# Sch_Power.net
KiCad netlist of a schematic drawn in Altium Designer
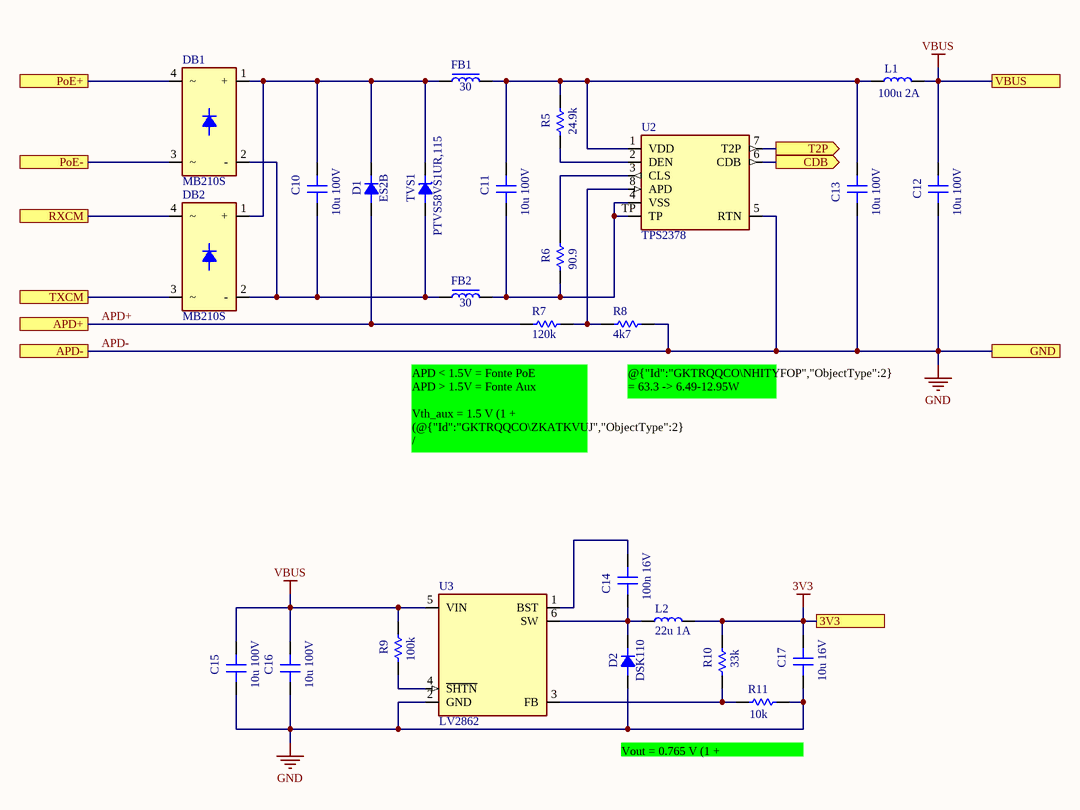
[diagram p0: Sch_Power.SchDoc]

(export (version "E")
  (design (tool "Eeschema 10.0.6"))
  (components
    (comp (ref "C10")
      (value "10u 100V")
      (footprint "CAP_SMD_1210")
      (description "Capacitor SMD - Generic")
      (libsource (lib "AltiumLibrary") (part "CAP_SMD"))
    )
    (comp (ref "C11")
      (value "10u 100V")
      (footprint "CAP_SMD_1210")
      (description "Capacitor SMD - Generic")
      (libsource (lib "AltiumLibrary") (part "CAP_SMD"))
    )
    (comp (ref "C12")
      (value "10u 100V")
      (footprint "CAP_SMD_1210")
      (description "Capacitor SMD - Generic")
      (libsource (lib "AltiumLibrary") (part "CAP_SMD"))
    )
    (comp (ref "C13")
      (value "10u 100V")
      (footprint "CAP_SMD_1210")
      (description "Capacitor SMD - Generic")
      (libsource (lib "AltiumLibrary") (part "CAP_SMD"))
    )
    (comp (ref "C14")
      (value "100n 16V")
      (footprint "CAP_SMD_0603")
      (description "Capacitor SMD - Generic")
      (libsource (lib "AltiumLibrary") (part "CAP_SMD"))
    )
    (comp (ref "C15")
      (value "10u 100V")
      (footprint "CAP_SMD_1210")
      (description "Capacitor SMD - Generic")
      (libsource (lib "AltiumLibrary") (part "CAP_SMD"))
    )
    (comp (ref "C16")
      (value "10u 100V")
      (footprint "CAP_SMD_1210")
      (description "Capacitor SMD - Generic")
      (libsource (lib "AltiumLibrary") (part "CAP_SMD"))
    )
    (comp (ref "C17")
      (value "10u 16V")
      (footprint "CAP_SMD_1210")
      (description "Capacitor SMD - Generic")
      (libsource (lib "AltiumLibrary") (part "CAP_SMD"))
    )
    (comp (ref "D1")
      (value "ES2B")
      (footprint "D_SMA")
      (description "100V 2A Super Fast Recovery Rectifier")
      (libsource (lib "AltiumLibrary") (part "ES1J"))
    )
    (comp (ref "D2")
      (value "DSK110")
      (footprint "D_SMD_SOD123W")
      (description "100V 1A Schottky Barrier Diode")
      (libsource (lib "AltiumLibrary") (part "DIODE_SMD"))
    )
    (comp (ref "DB1")
      (value "MB210S")
      (footprint "IC_MBS")
      (description "100 2A diode bridge")
      (fields (field (name "MF") "Fortune Semiconductor") (field (name "MP") "DW01A"))
      (libsource (lib "AltiumLibrary") (part "MB2S"))
    )
    (comp (ref "DB2")
      (value "MB210S")
      (footprint "IC_MBS")
      (description "100 2A diode bridge")
      (fields (field (name "MF") "Fortune Semiconductor") (field (name "MP") "DW01A"))
      (libsource (lib "AltiumLibrary") (part "MB2S"))
    )
    (comp (ref "FB1")
      (value "30")
      (footprint "FB_SMD_0805")
      (description "Ferrite bead SMD - Generic")
      (libsource (lib "AltiumLibrary") (part "FB_SMD"))
    )
    (comp (ref "FB2")
      (value "30")
      (footprint "FB_SMD_0805")
      (description "Ferrite bead SMD - Generic")
      (libsource (lib "AltiumLibrary") (part "FB_SMD"))
    )
    (comp (ref "L1")
      (value "100u 2A")
      (footprint "IND_SMD7.1x6.6x5")
      (description "Inductor SMD - Generic")
      (libsource (lib "AltiumLibrary") (part "IND_SMD"))
    )
    (comp (ref "L2")
      (value "22u 1A")
      (footprint "IND_SMD3x3x1.2mm")
      (description "Inductor SMD - Generic")
      (libsource (lib "AltiumLibrary") (part "IND_SMD"))
    )
    (comp (ref "R5")
      (value "24.9k")
      (footprint "RES_SMD_0603")
      (description "Resistor SMD - Generic")
      (libsource (lib "") (part "RES_SMD_1"))
    )
    (comp (ref "R6")
      (value "90.9")
      (footprint "RES_SMD_0603")
      (description "Resistor SMD - Generic")
      (libsource (lib "") (part "RES_SMD_1"))
    )
    (comp (ref "R7")
      (value "120k")
      (footprint "RES_SMD_0603")
      (description "Resistor SMD - Generic")
      (libsource (lib "AltiumLibrary") (part "RES_SMD"))
    )
    (comp (ref "R8")
      (value "4k7")
      (footprint "RES_SMD_0603")
      (description "Resistor SMD - Generic")
      (libsource (lib "AltiumLibrary") (part "RES_SMD"))
    )
    (comp (ref "R9")
      (value "100k")
      (footprint "RES_SMD_0603")
      (description "Resistor SMD - Generic")
      (libsource (lib "") (part "RES_SMD_1"))
    )
    (comp (ref "R10")
      (value "33k")
      (footprint "RES_SMD_0603")
      (description "Resistor SMD - Generic")
      (libsource (lib "") (part "RES_SMD_1"))
    )
    (comp (ref "R11")
      (value "10k")
      (footprint "RES_SMD_0603")
      (description "Resistor SMD - Generic")
      (libsource (lib "AltiumLibrary") (part "RES_SMD"))
    )
    (comp (ref "TVS1")
      (value "PTVS58VS1UR,115")
      (footprint "D_SOD123W")
      (description "SMD zener diode - Generic")
      (libsource (lib "AltiumLibrary") (part "ZENER_SMD"))
    )
    (comp (ref "U2")
      (value "TPS2378")
      (footprint "IC_SOIC8_TP")
      (description "IEEE 802.3at PoE High-Power PD Interface")
      (fields (field (name "MF") "Fortune Semiconductor") (field (name "MP") "DW01A"))
      (libsource (lib "AltiumLibrary") (part "TPS2378"))
    )
    (comp (ref "U3")
      (value "LV2862")
      (footprint "IC_SOT23_6")
      (description "Buck converter controller")
      (libsource (lib "AltiumLibrary") (part "LV2862"))
    )
  )
  (nets
    (net (code "1") (name "/APD+") (class "Default")
      (node (ref "D1") (pin "A") (pinfunction "A_A") (pintype "passive"))
      (node (ref "R7") (pin "1") (pinfunction "1_1") (pintype "passive"))
    )
    (net (code "2") (name "/CDB") (class "Default")
      (node (ref "U2") (pin "6") (pinfunction "CDB_6") (pintype "output"))
    )
    (net (code "3") (name "/PoE+") (class "Default")
      (node (ref "DB1") (pin "4") (pinfunction "~_4") (pintype "power_in"))
    )
    (net (code "4") (name "/PoE-") (class "Default")
      (node (ref "DB1") (pin "3") (pinfunction "~_3") (pintype "power_in"))
    )
    (net (code "5") (name "/RXCM") (class "Default")
      (node (ref "DB2") (pin "4") (pinfunction "~_4") (pintype "power_in"))
    )
    (net (code "6") (name "/T2P") (class "Default")
      (node (ref "U2") (pin "7") (pinfunction "T2P_7") (pintype "output"))
    )
    (net (code "7") (name "/TXCM") (class "Default")
      (node (ref "DB2") (pin "3") (pinfunction "~_3") (pintype "power_in"))
    )
    (net (code "8") (name "3V3") (class "Default")
      (node (ref "C17") (pin "1") (pinfunction "1_1") (pintype "passive"))
      (node (ref "L2") (pin "2") (pinfunction "2_2") (pintype "passive"))
      (node (ref "R10") (pin "1") (pinfunction "1_1") (pintype "passive"))
    )
    (net (code "9") (name "GND") (class "Default")
      (node (ref "C12") (pin "2") (pinfunction "2_2") (pintype "passive"))
      (node (ref "C13") (pin "2") (pinfunction "2_2") (pintype "passive"))
      (node (ref "C15") (pin "2") (pinfunction "2_2") (pintype "passive"))
      (node (ref "C16") (pin "2") (pinfunction "2_2") (pintype "passive"))
      (node (ref "C17") (pin "2") (pinfunction "2_2") (pintype "passive"))
      (node (ref "D2") (pin "A") (pinfunction "A_A") (pintype "passive"))
      (node (ref "R11") (pin "2") (pinfunction "2_2") (pintype "passive"))
      (node (ref "R8") (pin "2") (pinfunction "2_2") (pintype "passive"))
      (node (ref "U2") (pin "5") (pinfunction "RTN_5") (pintype "passive"))
      (node (ref "U3") (pin "2") (pinfunction "GND_2") (pintype "power_in"))
    )
    (net (code "10") (name "Net-(DB1-+)") (class "Default")
      (node (ref "C10") (pin "1") (pinfunction "1_1") (pintype "passive"))
      (node (ref "D1") (pin "K") (pinfunction "K_K") (pintype "passive"))
      (node (ref "DB1") (pin "1") (pinfunction "+_1") (pintype "power_in"))
      (node (ref "DB2") (pin "1") (pinfunction "+_1") (pintype "power_in"))
      (node (ref "FB1") (pin "1") (pinfunction "1_1") (pintype "passive"))
      (node (ref "TVS1") (pin "K") (pinfunction "K_K") (pintype "passive"))
    )
    (net (code "11") (name "Net-(DB1--)") (class "Default")
      (node (ref "C10") (pin "2") (pinfunction "2_2") (pintype "passive"))
      (node (ref "DB1") (pin "2") (pinfunction "-_2") (pintype "power_in"))
      (node (ref "DB2") (pin "2") (pinfunction "-_2") (pintype "power_in"))
      (node (ref "FB2") (pin "1") (pinfunction "1_1") (pintype "passive"))
      (node (ref "TVS1") (pin "A") (pinfunction "A_A") (pintype "passive"))
    )
    (net (code "12") (name "Net-(U2-APD)") (class "Default")
      (node (ref "R7") (pin "2") (pinfunction "2_2") (pintype "passive"))
      (node (ref "R8") (pin "1") (pinfunction "1_1") (pintype "passive"))
      (node (ref "U2") (pin "8") (pinfunction "APD_8") (pintype "input"))
    )
    (net (code "13") (name "Net-(U2-CLS)") (class "Default")
      (node (ref "R6") (pin "1") (pinfunction "1_1") (pintype "passive"))
      (node (ref "U2") (pin "3") (pinfunction "CLS_3") (pintype "output"))
    )
    (net (code "14") (name "Net-(U2-DEN)") (class "Default")
      (node (ref "R5") (pin "2") (pinfunction "2_2") (pintype "passive"))
      (node (ref "U2") (pin "2") (pinfunction "DEN_2") (pintype "bidirectional"))
    )
    (net (code "15") (name "Net-(U2-VDD)") (class "Default")
      (node (ref "C11") (pin "1") (pinfunction "1_1") (pintype "passive"))
      (node (ref "C13") (pin "1") (pinfunction "1_1") (pintype "passive"))
      (node (ref "FB1") (pin "2") (pinfunction "2_2") (pintype "passive"))
      (node (ref "L1") (pin "1") (pinfunction "1_1") (pintype "passive"))
      (node (ref "R5") (pin "1") (pinfunction "1_1") (pintype "passive"))
      (node (ref "U2") (pin "1") (pinfunction "VDD_1") (pintype "power_in"))
    )
    (net (code "16") (name "Net-(U2-VSS)") (class "Default")
      (node (ref "C11") (pin "2") (pinfunction "2_2") (pintype "passive"))
      (node (ref "FB2") (pin "2") (pinfunction "2_2") (pintype "passive"))
      (node (ref "R6") (pin "2") (pinfunction "2_2") (pintype "passive"))
      (node (ref "U2") (pin "4") (pinfunction "VSS_4") (pintype "power_in"))
      (node (ref "U2") (pin "TP") (pinfunction "TP_TP") (pintype "power_in"))
    )
    (net (code "17") (name "Net-(U3-BST)") (class "Default")
      (node (ref "C14") (pin "1") (pinfunction "1_1") (pintype "passive"))
      (node (ref "U3") (pin "1") (pinfunction "BST_1") (pintype "power_in"))
    )
    (net (code "18") (name "Net-(U3-FB)") (class "Default")
      (node (ref "R10") (pin "2") (pinfunction "2_2") (pintype "passive"))
      (node (ref "R11") (pin "1") (pinfunction "1_1") (pintype "passive"))
      (node (ref "U3") (pin "3") (pinfunction "FB_3") (pintype "passive"))
    )
    (net (code "19") (name "Net-(U3-SW)") (class "Default")
      (node (ref "C14") (pin "2") (pinfunction "2_2") (pintype "passive"))
      (node (ref "D2") (pin "K") (pinfunction "K_K") (pintype "passive"))
      (node (ref "L2") (pin "1") (pinfunction "1_1") (pintype "passive"))
      (node (ref "U3") (pin "6") (pinfunction "SW_6") (pintype "passive"))
    )
    (net (code "20") (name "Net-(U3-~{SHTN})") (class "Default")
      (node (ref "R9") (pin "2") (pinfunction "2_2") (pintype "passive"))
      (node (ref "U3") (pin "4") (pinfunction "~{SHTN}_4") (pintype "input"))
    )
    (net (code "21") (name "VBUS") (class "Default")
      (node (ref "C12") (pin "1") (pinfunction "1_1") (pintype "passive"))
      (node (ref "C15") (pin "1") (pinfunction "1_1") (pintype "passive"))
      (node (ref "C16") (pin "1") (pinfunction "1_1") (pintype "passive"))
      (node (ref "L1") (pin "2") (pinfunction "2_2") (pintype "passive"))
      (node (ref "R9") (pin "1") (pinfunction "1_1") (pintype "passive"))
      (node (ref "U3") (pin "5") (pinfunction "VIN_5") (pintype "power_in"))
    )
  )
)
